# Ethernet_Interface.net
KiCad netlist of a schematic drawn in Altium Designer
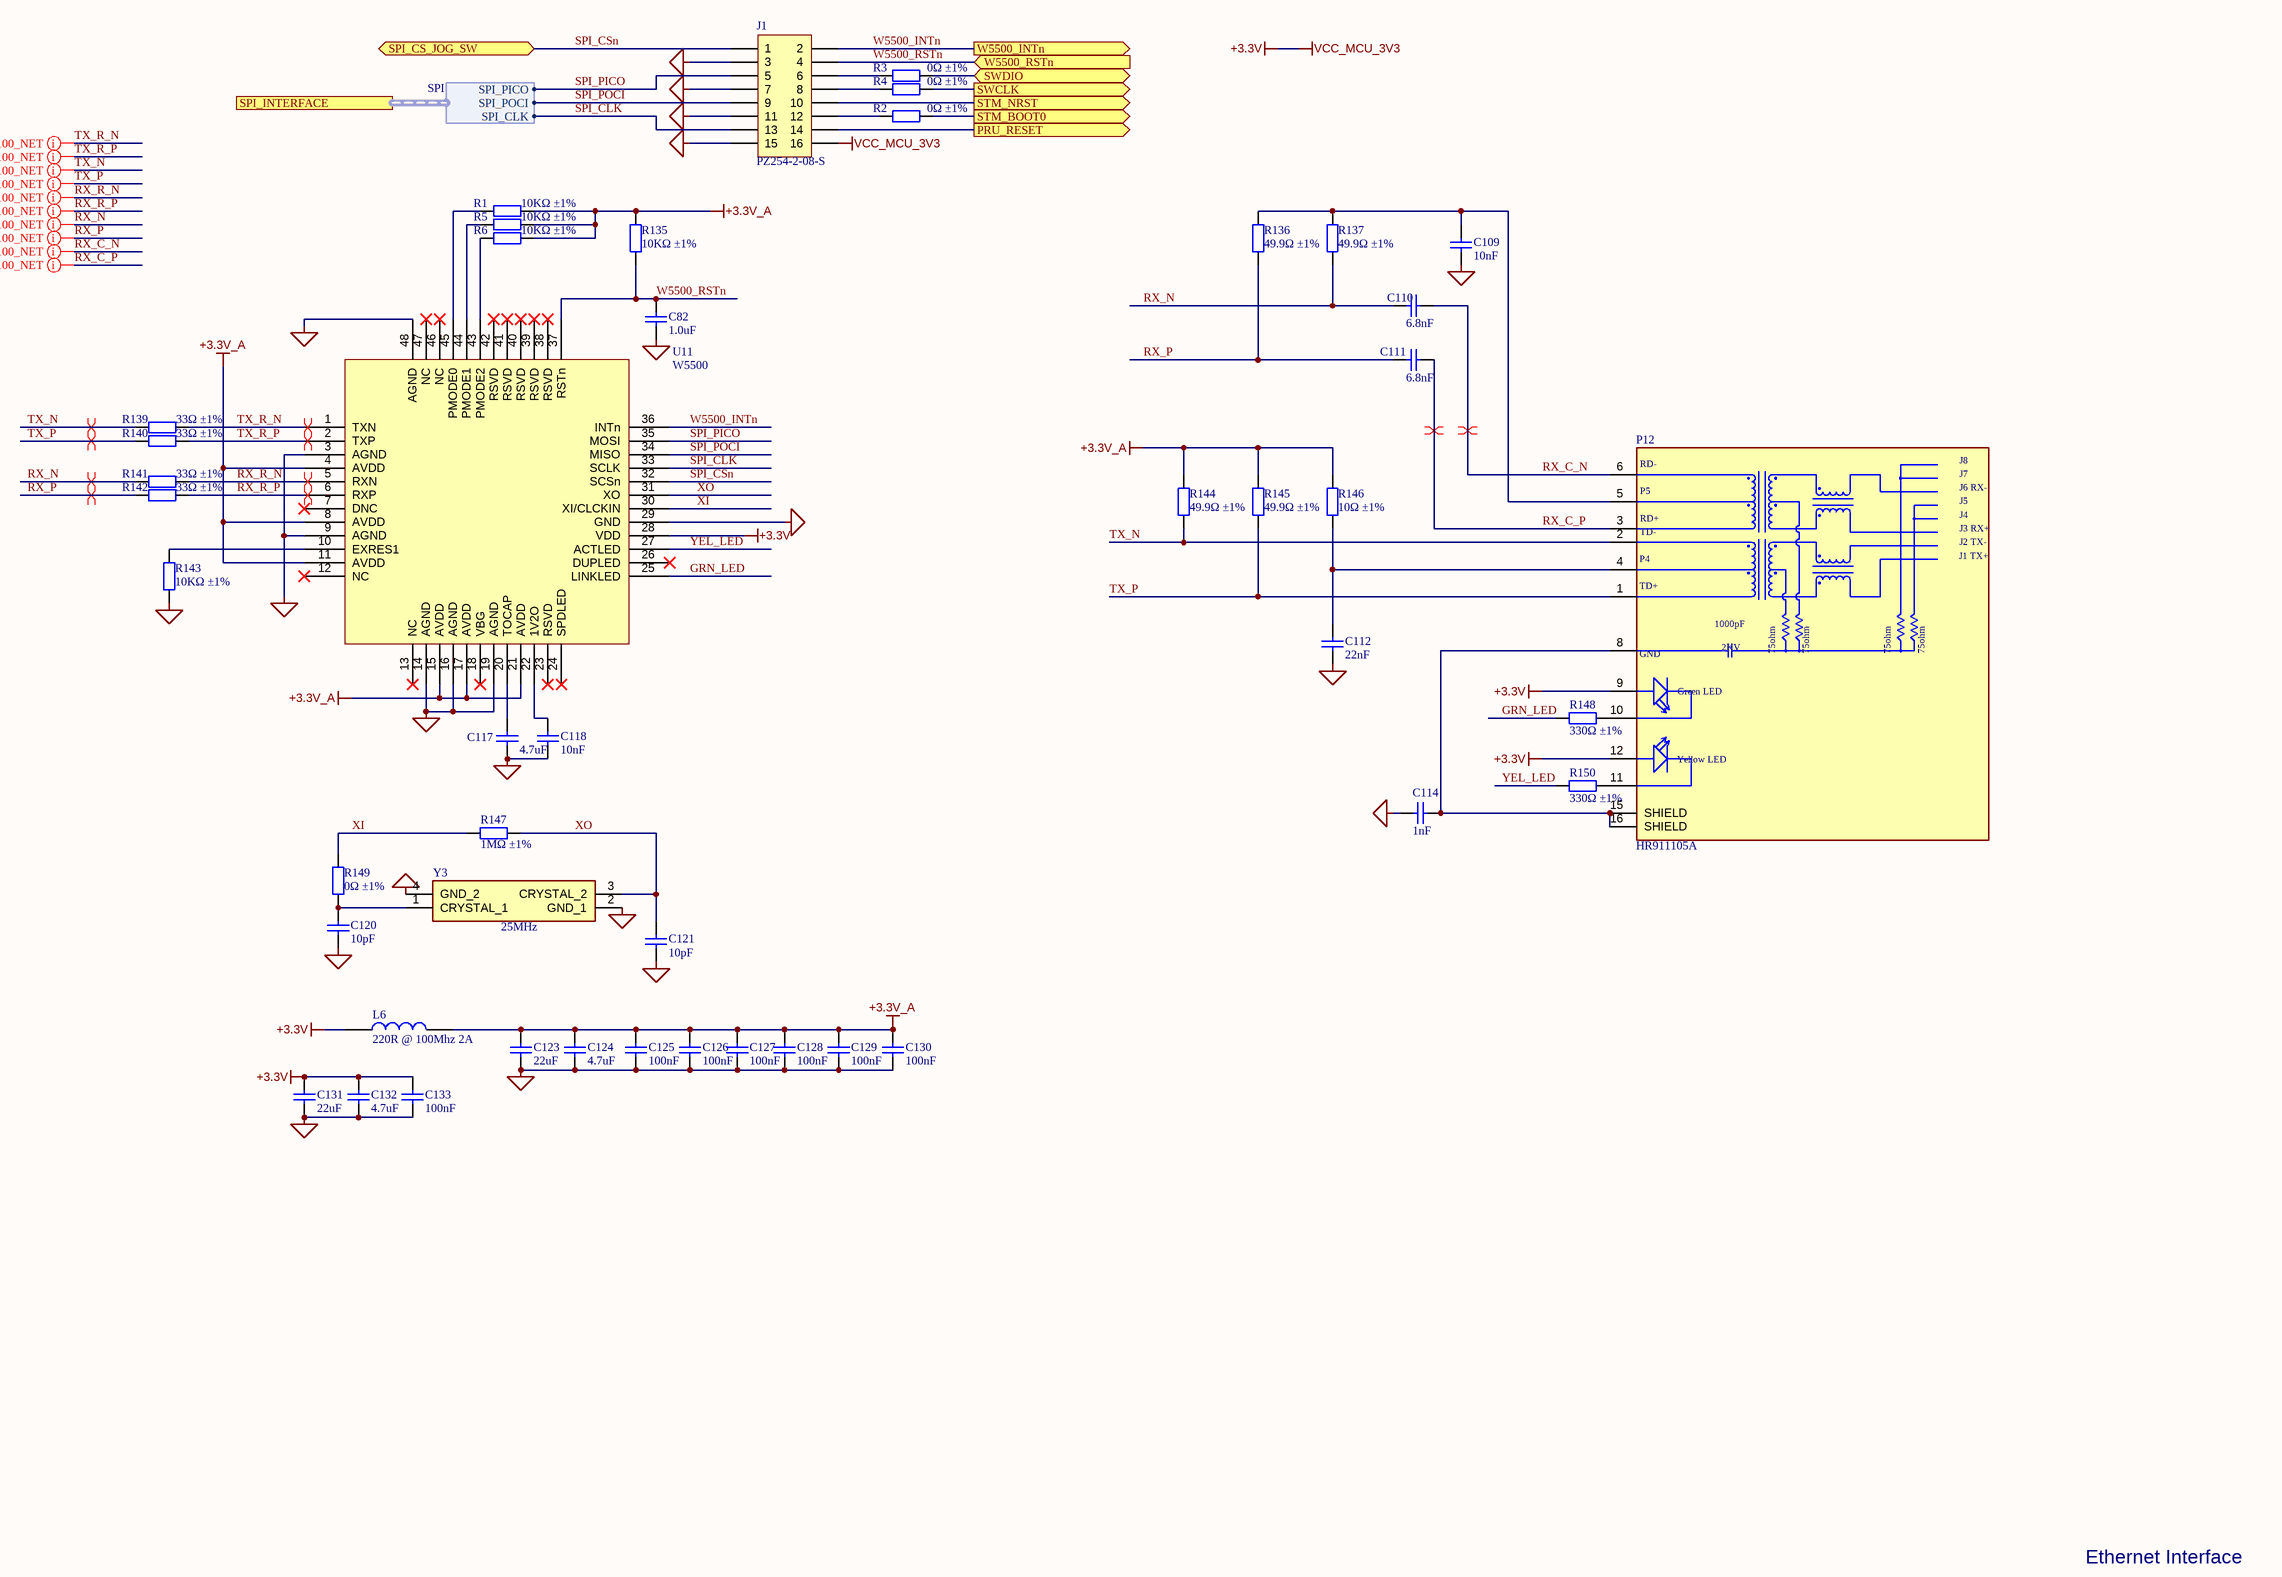
[diagram p0: Ethernet_Interface.SchDoc]

(export (version "E")
  (design (tool "Eeschema 10.0.6"))
  (components
    (comp (ref "C82")
      (value "1.0uF")
      (footprint "0402_C")
      (description "Chip capacitor")
      (fields (field (name "MANUFACTURER") "Samsung Electro-Mechanics") (field (name "TOLERANCE") "10%"))
      (libsource (lib "Cap") (part "0402 1.0uF (105) 10% 25V"))
    )
    (comp (ref "C109")
      (value "10nF")
      (footprint "0402_C")
      (description "Chip capacitors")
      (fields
        (field (name "MANUFACTURER") "Samsung Electro-Mechanics")
        (field (name "MANUFACTURER PART NUMBER") "CL05B103KB5NNNC")
      )
      (libsource (lib "Cap") (part "0402 10nF (103) 10% 50V"))
    )
    (comp (ref "C110")
      (value "6.8nF")
      (footprint "0402_C")
      (description "Chip capacitors")
      (fields
        (field (name "MANUFACTURER") "Guangdong Fenghua Advanced Tech")
        (field (name "MANUFACTURER PART NUMBER") "0402B682K500NT")
      )
      (libsource (lib "Cap") (part "0402 6.8nF (682) 10% 50V"))
    )
    (comp (ref "C111")
      (value "6.8nF")
      (footprint "0402_C")
      (description "Chip capacitors")
      (fields
        (field (name "MANUFACTURER") "Guangdong Fenghua Advanced Tech")
        (field (name "MANUFACTURER PART NUMBER") "0402B682K500NT")
      )
      (libsource (lib "Cap") (part "0402 6.8nF (682) 10% 50V"))
    )
    (comp (ref "C112")
      (value "22nF")
      (footprint "0402_C")
      (description "Chip capacitors")
      (fields
        (field (name "MANUFACTURER") "Guangdong Fenghua Advanced Tech")
        (field (name "MANUFACTURER PART NUMBER") "0402B223K500NT")
      )
      (libsource (lib "Cap") (part "0402 22nF (223) 10% 50V"))
    )
    (comp (ref "C114")
      (value "1nF")
      (footprint "1206_C")
      (description "Chip capacitors")
      (fields
        (field (name "MANUFACTURER") "Samsung Electro-Mechanics")
        (field (name "MANUFACTURER PART NUMBER") "CL31B102KGFNNNE")
      )
      (libsource (lib "Cap") (part "1206 1nF (102) 10% 500V"))
    )
    (comp (ref "C117")
      (value "4.7uF")
      (footprint "0402_C")
      (description "Chip capacitor")
      (fields
        (field (name "MANUFACTURER") "Samsung Electro-Mechanics")
        (field (name "MANUFACTURER PART NUMBER") "CL05A475MP5NRNC")
      )
      (libsource (lib "Cap") (part "0402 4.7uF (475) 20% 10V"))
    )
    (comp (ref "C118")
      (value "10nF")
      (footprint "0402_C")
      (description "Chip capacitors")
      (fields
        (field (name "MANUFACTURER") "Samsung Electro-Mechanics")
        (field (name "MANUFACTURER PART NUMBER") "CL05B103KB5NNNC")
      )
      (libsource (lib "Cap") (part "0402 10nF (103) 10% 50V"))
    )
    (comp (ref "C120")
      (value "10pF")
      (footprint "0402_C")
      (description "Chip capacitors")
      (fields
        (field (name "MANUFACTURER") "Murata Electronics")
        (field (name "MANUFACTURER PART NUMBER") "GRM1555C1H100JA01D")
      )
      (libsource (lib "Sienci_Labs") (part "0402 10pF (100) 5% 50V"))
    )
    (comp (ref "C121")
      (value "10pF")
      (footprint "0402_C")
      (description "Chip capacitors")
      (fields
        (field (name "MANUFACTURER") "Murata Electronics")
        (field (name "MANUFACTURER PART NUMBER") "GRM1555C1H100JA01D")
      )
      (libsource (lib "Sienci_Labs") (part "0402 10pF (100) 5% 50V"))
    )
    (comp (ref "C123")
      (value "22uF")
      (footprint "0805_C")
      (description "25V 22uF X5R ±20% 0805 Multilayer Ceramic Capacitors MLCC - SMD/SMT ROHS")
      (fields (field (name "MANUFACTURER") "Samsung Electro-Mechanics") (field (name "TOLERANCE") "20%"))
      (libsource (lib "Sienci_Labs") (part "0805 22uF (226) 20% 25V"))
    )
    (comp (ref "C124")
      (value "4.7uF")
      (footprint "0603_C")
      (description "16V 4.7uF X5R ±10% 0603 Multilayer Ceramic Capacitors MLCC - SMD/SMT ROHS")
      (fields (field (name "MANUFACTURER") "Samsung Electro-Mechanics") (field (name "TOLERANCE") "10%"))
      (libsource (lib "Sienci_Labs") (part "0603 4.7uF (475) 10% 16V"))
    )
    (comp (ref "C125")
      (value "100nF")
      (footprint "0402_C")
      (description "16V 100nF X7R ±10% 0402 Multilayer Ceramic Capacitors MLCC - SMD/SMT ROHS")
      (fields (field (name "MANUFACTURER") "Samsung Electro-Mechanics") (field (name "TOLERANCE") "10%"))
      (libsource (lib "Sienci_Labs") (part "0402 100nF (104) 10% 16V"))
    )
    (comp (ref "C126")
      (value "100nF")
      (footprint "0402_C")
      (description "16V 100nF X7R ±10% 0402 Multilayer Ceramic Capacitors MLCC - SMD/SMT ROHS")
      (fields (field (name "MANUFACTURER") "Samsung Electro-Mechanics") (field (name "TOLERANCE") "10%"))
      (libsource (lib "Sienci_Labs") (part "0402 100nF (104) 10% 16V"))
    )
    (comp (ref "C127")
      (value "100nF")
      (footprint "0402_C")
      (description "16V 100nF X7R ±10% 0402 Multilayer Ceramic Capacitors MLCC - SMD/SMT ROHS")
      (fields (field (name "MANUFACTURER") "Samsung Electro-Mechanics") (field (name "TOLERANCE") "10%"))
      (libsource (lib "Sienci_Labs") (part "0402 100nF (104) 10% 16V"))
    )
    (comp (ref "C128")
      (value "100nF")
      (footprint "0402_C")
      (description "16V 100nF X7R ±10% 0402 Multilayer Ceramic Capacitors MLCC - SMD/SMT ROHS")
      (fields (field (name "MANUFACTURER") "Samsung Electro-Mechanics") (field (name "TOLERANCE") "10%"))
      (libsource (lib "Sienci_Labs") (part "0402 100nF (104) 10% 16V"))
    )
    (comp (ref "C129")
      (value "100nF")
      (footprint "0402_C")
      (description "16V 100nF X7R ±10% 0402 Multilayer Ceramic Capacitors MLCC - SMD/SMT ROHS")
      (fields (field (name "MANUFACTURER") "Samsung Electro-Mechanics") (field (name "TOLERANCE") "10%"))
      (libsource (lib "Sienci_Labs") (part "0402 100nF (104) 10% 16V"))
    )
    (comp (ref "C130")
      (value "100nF")
      (footprint "0402_C")
      (description "16V 100nF X7R ±10% 0402 Multilayer Ceramic Capacitors MLCC - SMD/SMT ROHS")
      (fields (field (name "MANUFACTURER") "Samsung Electro-Mechanics") (field (name "TOLERANCE") "10%"))
      (libsource (lib "Sienci_Labs") (part "0402 100nF (104) 10% 16V"))
    )
    (comp (ref "C131")
      (value "22uF")
      (footprint "0805_C")
      (description "25V 22uF X5R ±20% 0805 Multilayer Ceramic Capacitors MLCC - SMD/SMT ROHS")
      (fields (field (name "MANUFACTURER") "Samsung Electro-Mechanics") (field (name "TOLERANCE") "20%"))
      (libsource (lib "Sienci_Labs") (part "0805 22uF (226) 20% 25V"))
    )
    (comp (ref "C132")
      (value "4.7uF")
      (footprint "0603_C")
      (description "16V 4.7uF X5R ±10% 0603 Multilayer Ceramic Capacitors MLCC - SMD/SMT ROHS")
      (fields (field (name "MANUFACTURER") "Samsung Electro-Mechanics") (field (name "TOLERANCE") "10%"))
      (libsource (lib "Sienci_Labs") (part "0603 4.7uF (475) 10% 16V"))
    )
    (comp (ref "C133")
      (value "100nF")
      (footprint "0402_C")
      (description "16V 100nF X7R ±10% 0402 Multilayer Ceramic Capacitors MLCC - SMD/SMT ROHS")
      (fields (field (name "MANUFACTURER") "Samsung Electro-Mechanics") (field (name "TOLERANCE") "10%"))
      (libsource (lib "Sienci_Labs") (part "0402 100nF (104) 10% 16V"))
    )
    (comp (ref "J1")
      (value "PZ254-2-08-S")
      (footprint "95278101A16LF")
      (fields (field (name "MANUFACTURER") "HCTL"))
      (libsource (lib "Sienci_Labs") (part "PZ254-2-08-S"))
    )
    (comp (ref "L6")
      (value "220R @ 100Mhz 2A")
      (footprint "0805_R")
      (description "150mΩ ±25% 220Ω@100MHz 0805 Ferrite Beads ROHS")
      (fields
        (field (name "MANUFACTURER PART NUMBER") "CBW201209U221T")
        (field (name "MANUFACTURER") "FH (Guangdong Fenghua Advanced Tech)")
      )
      (libsource (lib "Sienci_Labs") (part "CBW201209U221T"))
    )
    (comp (ref "P12")
      (value "HR911105A")
      (footprint "HANRUN_HR911105A")
      (description "HR911105A Ethernet Interface Arduino Platform Evaluation Expansion Board")
      (fields (field (name "MANUFACTURER") "DFRobot"))
      (libsource (lib "Sienci_Labs") (part "HR911105A"))
    )
    (comp (ref "R1")
      (value "10KΩ ±1%")
      (footprint "0402_R")
      (description "Chip resistor")
      (fields
        (field (name "MANUFACTURER") "Uniroyal Elec")
        (field (name "MANUFACTURER PART NUMBER") "0402WGF1002TCE")
      )
      (libsource (lib "Sienci_Labs") (part "0402 10K (1002) 1%"))
    )
    (comp (ref "R2")
      (value "0Ω ±1%")
      (footprint "0603_R")
      (description "Chip resistor")
      (fields
        (field (name "MANUFACTURER") "Uniroyal Elec")
        (field (name "MANUFACTURER PART NUMBER") "0603WAF0000T5E")
      )
      (libsource (lib "Sienci_Labs") (part "0603 0R (0R0) 1%"))
    )
    (comp (ref "R3")
      (value "0Ω ±1%")
      (footprint "0603_R")
      (description "Chip resistor")
      (fields
        (field (name "MANUFACTURER") "Uniroyal Elec")
        (field (name "MANUFACTURER PART NUMBER") "0603WAF0000T5E")
      )
      (libsource (lib "Sienci_Labs") (part "0603 0R (0R0) 1%"))
    )
    (comp (ref "R4")
      (value "0Ω ±1%")
      (footprint "0603_R")
      (description "Chip resistor")
      (fields
        (field (name "MANUFACTURER") "Uniroyal Elec")
        (field (name "MANUFACTURER PART NUMBER") "0603WAF0000T5E")
      )
      (libsource (lib "Sienci_Labs") (part "0603 0R (0R0) 1%"))
    )
    (comp (ref "R5")
      (value "10KΩ ±1%")
      (footprint "0402_R")
      (description "Chip resistor")
      (fields
        (field (name "MANUFACTURER") "Uniroyal Elec")
        (field (name "MANUFACTURER PART NUMBER") "0402WGF1002TCE")
      )
      (libsource (lib "Sienci_Labs") (part "0402 10K (1002) 1%"))
    )
    (comp (ref "R6")
      (value "10KΩ ±1%")
      (footprint "0402_R")
      (description "Chip resistor")
      (fields
        (field (name "MANUFACTURER") "Uniroyal Elec")
        (field (name "MANUFACTURER PART NUMBER") "0402WGF1002TCE")
      )
      (libsource (lib "Sienci_Labs") (part "0402 10K (1002) 1%"))
    )
    (comp (ref "R135")
      (value "10KΩ ±1%")
      (footprint "0402_R")
      (description "Chip resistor")
      (fields
        (field (name "MANUFACTURER") "Uniroyal Elec")
        (field (name "MANUFACTURER PART NUMBER") "0402WGF1002TCE")
      )
      (libsource (lib "") (part "0402 10K (1002) 1%_1"))
    )
    (comp (ref "R136")
      (value "49.9Ω ±1%")
      (footprint "0402_R")
      (description "Chip resistor")
      (fields
        (field (name "MANUFACTURER") "Uniroyal Elec")
        (field (name "MANUFACTURER PART NUMBER") "0402WGF499JTCE")
      )
      (libsource (lib "RES") (part "0402 49.9R (49R9) 1%"))
    )
    (comp (ref "R137")
      (value "49.9Ω ±1%")
      (footprint "0402_R")
      (description "Chip resistor")
      (fields
        (field (name "MANUFACTURER") "Uniroyal Elec")
        (field (name "MANUFACTURER PART NUMBER") "0402WGF499JTCE")
      )
      (libsource (lib "RES") (part "0402 49.9R (49R9) 1%"))
    )
    (comp (ref "R139")
      (value "33Ω ±1%")
      (footprint "0402_R")
      (description "Chip resistor")
      (fields
        (field (name "MANUFACTURER") "Uniroyal Elec")
        (field (name "MANUFACTURER PART NUMBER") "0402WGF330JTCE")
      )
      (libsource (lib "RES") (part "0402 33R (33R0) 1%"))
    )
    (comp (ref "R140")
      (value "33Ω ±1%")
      (footprint "0402_R")
      (description "Chip resistor")
      (fields
        (field (name "MANUFACTURER") "Uniroyal Elec")
        (field (name "MANUFACTURER PART NUMBER") "0402WGF330JTCE")
      )
      (libsource (lib "RES") (part "0402 33R (33R0) 1%"))
    )
    (comp (ref "R141")
      (value "33Ω ±1%")
      (footprint "0402_R")
      (description "Chip resistor")
      (fields
        (field (name "MANUFACTURER") "Uniroyal Elec")
        (field (name "MANUFACTURER PART NUMBER") "0402WGF330JTCE")
      )
      (libsource (lib "RES") (part "0402 33R (33R0) 1%"))
    )
    (comp (ref "R142")
      (value "33Ω ±1%")
      (footprint "0402_R")
      (description "Chip resistor")
      (fields
        (field (name "MANUFACTURER") "Uniroyal Elec")
        (field (name "MANUFACTURER PART NUMBER") "0402WGF330JTCE")
      )
      (libsource (lib "RES") (part "0402 33R (33R0) 1%"))
    )
    (comp (ref "R143")
      (value "10KΩ ±1%")
      (footprint "0603_R")
      (description "Chip resistor")
      (fields
        (field (name "MANUFACTURER") "Uniroyal Elec")
        (field (name "MANUFACTURER PART NUMBER") "0603WAF1002T5E")
      )
      (libsource (lib "Sienci_Labs") (part "0603 10K (1002) 1%"))
    )
    (comp (ref "R144")
      (value "49.9Ω ±1%")
      (footprint "0402_R")
      (description "Chip resistor")
      (fields
        (field (name "MANUFACTURER") "Uniroyal Elec")
        (field (name "MANUFACTURER PART NUMBER") "0402WGF499JTCE")
      )
      (libsource (lib "RES") (part "0402 49.9R (49R9) 1%"))
    )
    (comp (ref "R145")
      (value "49.9Ω ±1%")
      (footprint "0402_R")
      (description "Chip resistor")
      (fields
        (field (name "MANUFACTURER") "Uniroyal Elec")
        (field (name "MANUFACTURER PART NUMBER") "0402WGF499JTCE")
      )
      (libsource (lib "RES") (part "0402 49.9R (49R9) 1%"))
    )
    (comp (ref "R146")
      (value "10Ω ±1%")
      (footprint "0402_R")
      (description "Chip resistor")
      (fields
        (field (name "MANUFACTURER") "Uniroyal Elec")
        (field (name "MANUFACTURER PART NUMBER") "0402WGF100JTCE")
      )
      (libsource (lib "RES") (part "0402 10R (10R0) 1%"))
    )
    (comp (ref "R147")
      (value "1MΩ ±1%")
      (footprint "0402_R")
      (description "Chip resistor")
      (fields
        (field (name "MANUFACTURER") "Uniroyal Elec")
        (field (name "MANUFACTURER PART NUMBER") "0402WGF1004TCE")
      )
      (libsource (lib "RES") (part "0402 1M (1004) 1%"))
    )
    (comp (ref "R148")
      (value "330Ω ±1%")
      (footprint "0402_R")
      (description "Chip resistor")
      (fields
        (field (name "MANUFACTURER") "Uniroyal Elec")
        (field (name "MANUFACTURER PART NUMBER") "0402WGF3300TCE")
      )
      (libsource (lib "RES") (part "0402 330R (3300) 1%"))
    )
    (comp (ref "R149")
      (value "0Ω ±1%")
      (footprint "0402_R")
      (description "Chip resistor")
      (fields
        (field (name "MANUFACTURER") "Uniroyal Elec")
        (field (name "MANUFACTURER PART NUMBER") "0402WGF0000TCE")
      )
      (libsource (lib "RES") (part "0402 0R (0R0) 1%"))
    )
    (comp (ref "R150")
      (value "330Ω ±1%")
      (footprint "0402_R")
      (description "Chip resistor")
      (fields
        (field (name "MANUFACTURER") "Uniroyal Elec")
        (field (name "MANUFACTURER PART NUMBER") "0402WGF3300TCE")
      )
      (libsource (lib "RES") (part "0402 330R (3300) 1%"))
    )
    (comp (ref "U11")
      (value "W5500")
      (footprint "LQFP-48_7x7x05P")
      (description "Ethernet Controllers 2.97V ~ 3.63V 10/100 Base-T/TX PHY SPI LQFP-48_7x7x05P Ethernet ICs ROHS")
      (fields (field (name "MANUFACTURER") "WIZNET"))
      (libsource (lib "Sienci_Labs") (part "W5500_[C32843]"))
    )
    (comp (ref "Y3")
      (value "25MHz")
      (footprint "YSX321SL")
      (description "25MHz SMD Crystal Resonator 20pF ±10ppm ±30ppm -40℃~+85℃ SMD3225-4P Crystals ROHS")
      (fields
        (field (name "MANUFACTURER") "Yangxing Tech")
        (field (name "MANUFACTURER PART NUMBER") "X322525MSB4SI")
      )
      (libsource (lib "Sienci_Labs") (part "X322525MSB4SI"))
    )
  )
  (nets
    (net (code "2") (name "+3.3V") (class "Default")
      (node (ref "C131") (pin "2") (pinfunction "2_2") (pintype "passive"))
      (node (ref "C132") (pin "2") (pinfunction "2_2") (pintype "passive"))
      (node (ref "C133") (pin "2") (pinfunction "2_2") (pintype "passive"))
      (node (ref "J1") (pin "16") (pinfunction "16_16") (pintype "passive"))
      (node (ref "L6") (pin "1") (pinfunction "1_1") (pintype "passive"))
      (node (ref "P12") (pin "12") (pinfunction "YA_12") (pintype "passive"))
      (node (ref "P12") (pin "9") (pinfunction "GA_9") (pintype "passive"))
      (node (ref "U11") (pin "28") (pinfunction "VDD_28") (pintype "passive"))
    )
    (net (code "3") (name "+3.3V_A") (class "Default")
      (node (ref "C123") (pin "2") (pinfunction "2_2") (pintype "passive"))
      (node (ref "C124") (pin "2") (pinfunction "2_2") (pintype "passive"))
      (node (ref "C125") (pin "2") (pinfunction "2_2") (pintype "passive"))
      (node (ref "C126") (pin "2") (pinfunction "2_2") (pintype "passive"))
      (node (ref "C127") (pin "2") (pinfunction "2_2") (pintype "passive"))
      (node (ref "C128") (pin "2") (pinfunction "2_2") (pintype "passive"))
      (node (ref "C129") (pin "2") (pinfunction "2_2") (pintype "passive"))
      (node (ref "C130") (pin "2") (pinfunction "2_2") (pintype "passive"))
      (node (ref "L6") (pin "2") (pinfunction "2_2") (pintype "passive"))
      (node (ref "R1") (pin "1") (pinfunction "1_1") (pintype "passive"))
      (node (ref "R135") (pin "1") (pinfunction "1_1") (pintype "passive"))
      (node (ref "R144") (pin "1") (pinfunction "1_1") (pintype "passive"))
      (node (ref "R145") (pin "1") (pinfunction "1_1") (pintype "passive"))
      (node (ref "R146") (pin "1") (pinfunction "1_1") (pintype "passive"))
      (node (ref "R5") (pin "1") (pinfunction "1_1") (pintype "passive"))
      (node (ref "R6") (pin "1") (pinfunction "1_1") (pintype "passive"))
      (node (ref "U11") (pin "11") (pinfunction "AVDD_11") (pintype "passive"))
      (node (ref "U11") (pin "15") (pinfunction "AVDD_15") (pintype "passive"))
      (node (ref "U11") (pin "17") (pinfunction "AVDD_17") (pintype "passive"))
      (node (ref "U11") (pin "21") (pinfunction "AVDD_21") (pintype "passive"))
      (node (ref "U11") (pin "4") (pinfunction "AVDD_4") (pintype "passive"))
      (node (ref "U11") (pin "8") (pinfunction "AVDD_8") (pintype "passive"))
    )
    (net (code "4") (name "/GRN_LED") (class "Default")
      (node (ref "R148") (pin "1") (pinfunction "1_1") (pintype "passive"))
      (node (ref "U11") (pin "25") (pinfunction "LINKLED_25") (pintype "passive"))
    )
    (net (code "5") (name "/PRU_RESET") (class "Default")
      (node (ref "J1") (pin "14") (pinfunction "14_14") (pintype "passive"))
    )
    (net (code "6") (name "/RX_C_N") (class "Default")
      (node (ref "C110") (pin "1") (pinfunction "1_1") (pintype "passive"))
      (node (ref "P12") (pin "6") (pinfunction "RD-_6") (pintype "passive"))
    )
    (net (code "7") (name "/RX_C_P") (class "Default")
      (node (ref "C111") (pin "1") (pinfunction "1_1") (pintype "passive"))
      (node (ref "P12") (pin "3") (pinfunction "RD+_3") (pintype "passive"))
    )
    (net (code "8") (name "/RX_N") (class "Default")
      (node (ref "C110") (pin "2") (pinfunction "2_2") (pintype "passive"))
      (node (ref "R137") (pin "2") (pinfunction "2_2") (pintype "passive"))
      (node (ref "R141") (pin "1") (pinfunction "1_1") (pintype "passive"))
    )
    (net (code "9") (name "/RX_P") (class "Default")
      (node (ref "C111") (pin "2") (pinfunction "2_2") (pintype "passive"))
      (node (ref "R136") (pin "2") (pinfunction "2_2") (pintype "passive"))
      (node (ref "R142") (pin "1") (pinfunction "1_1") (pintype "passive"))
    )
    (net (code "10") (name "/RX_R_N") (class "Default")
      (node (ref "R141") (pin "2") (pinfunction "2_2") (pintype "passive"))
      (node (ref "U11") (pin "5") (pinfunction "RXN_5") (pintype "passive"))
    )
    (net (code "11") (name "/RX_R_P") (class "Default")
      (node (ref "R142") (pin "2") (pinfunction "2_2") (pintype "passive"))
      (node (ref "U11") (pin "6") (pinfunction "RXP_6") (pintype "passive"))
    )
    (net (code "12") (name "/SPI_CLK") (class "Default")
      (node (ref "J1") (pin "13") (pinfunction "13_13") (pintype "passive"))
      (node (ref "U11") (pin "33") (pinfunction "SCLK_33") (pintype "passive"))
    )
    (net (code "13") (name "/SPI_CSn") (class "Default")
      (node (ref "J1") (pin "1") (pinfunction "1_1") (pintype "passive"))
      (node (ref "U11") (pin "32") (pinfunction "SCSn_32") (pintype "passive"))
    )
    (net (code "14") (name "/SPI_PICO") (class "Default")
      (node (ref "J1") (pin "5") (pinfunction "5_5") (pintype "passive"))
      (node (ref "U11") (pin "35") (pinfunction "MOSI_35") (pintype "passive"))
    )
    (net (code "15") (name "/SPI_POCI") (class "Default")
      (node (ref "J1") (pin "9") (pinfunction "9_9") (pintype "passive"))
      (node (ref "U11") (pin "34") (pinfunction "MISO_34") (pintype "passive"))
    )
    (net (code "16") (name "/STM_BOOT0") (class "Default")
      (node (ref "R2") (pin "1") (pinfunction "1_1") (pintype "passive"))
    )
    (net (code "17") (name "/STM_NRST") (class "Default")
      (node (ref "J1") (pin "10") (pinfunction "10_10") (pintype "passive"))
    )
    (net (code "18") (name "/SWCLK") (class "Default")
      (node (ref "R4") (pin "1") (pinfunction "1_1") (pintype "passive"))
    )
    (net (code "19") (name "/SWDIO") (class "Default")
      (node (ref "R3") (pin "1") (pinfunction "1_1") (pintype "passive"))
    )
    (net (code "20") (name "/TX_N") (class "Default")
      (node (ref "P12") (pin "2") (pinfunction "TD-_2") (pintype "passive"))
      (node (ref "R139") (pin "1") (pinfunction "1_1") (pintype "passive"))
      (node (ref "R144") (pin "2") (pinfunction "2_2") (pintype "passive"))
    )
    (net (code "21") (name "/TX_P") (class "Default")
      (node (ref "P12") (pin "1") (pinfunction "TD+_1") (pintype "passive"))
      (node (ref "R140") (pin "1") (pinfunction "1_1") (pintype "passive"))
      (node (ref "R145") (pin "2") (pinfunction "2_2") (pintype "passive"))
    )
    (net (code "22") (name "/TX_R_N") (class "Default")
      (node (ref "R139") (pin "2") (pinfunction "2_2") (pintype "passive"))
      (node (ref "U11") (pin "1") (pinfunction "TXN_1") (pintype "passive"))
    )
    (net (code "23") (name "/TX_R_P") (class "Default")
      (node (ref "R140") (pin "2") (pinfunction "2_2") (pintype "passive"))
      (node (ref "U11") (pin "2") (pinfunction "TXP_2") (pintype "passive"))
    )
    (net (code "24") (name "/W5500_INTn") (class "Default")
      (node (ref "J1") (pin "2") (pinfunction "2_2") (pintype "passive"))
      (node (ref "U11") (pin "36") (pinfunction "INTn_36") (pintype "passive"))
    )
    (net (code "25") (name "/W5500_RSTn") (class "Default")
      (node (ref "C82") (pin "2") (pinfunction "2_2") (pintype "passive"))
      (node (ref "J1") (pin "4") (pinfunction "4_4") (pintype "passive"))
      (node (ref "R135") (pin "2") (pinfunction "2_2") (pintype "passive"))
      (node (ref "U11") (pin "37") (pinfunction "RSTn_37") (pintype "passive"))
    )
    (net (code "26") (name "/XI") (class "Default")
      (node (ref "R147") (pin "1") (pinfunction "1_1") (pintype "passive"))
      (node (ref "R149") (pin "1") (pinfunction "1_1") (pintype "passive"))
      (node (ref "U11") (pin "30") (pinfunction "XI/CLCKIN_30") (pintype "passive"))
    )
    (net (code "27") (name "/XO") (class "Default")
      (node (ref "C121") (pin "2") (pinfunction "2_2") (pintype "passive"))
      (node (ref "R147") (pin "2") (pinfunction "2_2") (pintype "passive"))
      (node (ref "U11") (pin "31") (pinfunction "XO_31") (pintype "passive"))
      (node (ref "Y3") (pin "3") (pinfunction "CRYSTAL_2_3") (pintype "passive"))
    )
    (net (code "28") (name "/YEL_LED") (class "Default")
      (node (ref "R150") (pin "1") (pinfunction "1_1") (pintype "passive"))
      (node (ref "U11") (pin "27") (pinfunction "ACTLED_27") (pintype "passive"))
    )
    (net (code "30") (name "MCU_GND") (class "Default")
      (node (ref "C109") (pin "1") (pinfunction "1_1") (pintype "passive"))
      (node (ref "C112") (pin "1") (pinfunction "1_1") (pintype "passive"))
      (node (ref "C114") (pin "1") (pinfunction "1_1") (pintype "passive"))
      (node (ref "C117") (pin "1") (pinfunction "1_1") (pintype "passive"))
      (node (ref "C118") (pin "1") (pinfunction "1_1") (pintype "passive"))
      (node (ref "C120") (pin "1") (pinfunction "1_1") (pintype "passive"))
      (node (ref "C121") (pin "1") (pinfunction "1_1") (pintype "passive"))
      (node (ref "C123") (pin "1") (pinfunction "1_1") (pintype "passive"))
      (node (ref "C124") (pin "1") (pinfunction "1_1") (pintype "passive"))
      (node (ref "C125") (pin "1") (pinfunction "1_1") (pintype "passive"))
      (node (ref "C126") (pin "1") (pinfunction "1_1") (pintype "passive"))
      (node (ref "C127") (pin "1") (pinfunction "1_1") (pintype "passive"))
      (node (ref "C128") (pin "1") (pinfunction "1_1") (pintype "passive"))
      (node (ref "C129") (pin "1") (pinfunction "1_1") (pintype "passive"))
      (node (ref "C130") (pin "1") (pinfunction "1_1") (pintype "passive"))
      (node (ref "C131") (pin "1") (pinfunction "1_1") (pintype "passive"))
      (node (ref "C132") (pin "1") (pinfunction "1_1") (pintype "passive"))
      (node (ref "C133") (pin "1") (pinfunction "1_1") (pintype "passive"))
      (node (ref "C82") (pin "1") (pinfunction "1_1") (pintype "passive"))
      (node (ref "J1") (pin "11") (pinfunction "11_11") (pintype "passive"))
      (node (ref "J1") (pin "15") (pinfunction "15_15") (pintype "passive"))
      (node (ref "J1") (pin "3") (pinfunction "3_3") (pintype "passive"))
      (node (ref "J1") (pin "7") (pinfunction "7_7") (pintype "passive"))
      (node (ref "R143") (pin "1") (pinfunction "1_1") (pintype "passive"))
      (node (ref "U11") (pin "14") (pinfunction "AGND_14") (pintype "passive"))
      (node (ref "U11") (pin "16") (pinfunction "AGND_16") (pintype "passive"))
      (node (ref "U11") (pin "19") (pinfunction "AGND_19") (pintype "passive"))
      (node (ref "U11") (pin "29") (pinfunction "GND_29") (pintype "passive"))
      (node (ref "U11") (pin "3") (pinfunction "AGND_3") (pintype "passive"))
      (node (ref "U11") (pin "48") (pinfunction "AGND_48") (pintype "passive"))
      (node (ref "U11") (pin "9") (pinfunction "AGND_9") (pintype "passive"))
      (node (ref "Y3") (pin "2") (pinfunction "GND_1_2") (pintype "passive"))
      (node (ref "Y3") (pin "4") (pinfunction "GND_2_4") (pintype "passive"))
    )
    (net (code "31") (name "Net-(J1-Pad6)") (class "Default")
      (node (ref "J1") (pin "6") (pinfunction "6_6") (pintype "passive"))
      (node (ref "R3") (pin "2") (pinfunction "2_2") (pintype "passive"))
    )
    (net (code "32") (name "Net-(J1-Pad8)") (class "Default")
      (node (ref "J1") (pin "8") (pinfunction "8_8") (pintype "passive"))
      (node (ref "R4") (pin "2") (pinfunction "2_2") (pintype "passive"))
    )
    (net (code "33") (name "Net-(J1-Pad12)") (class "Default")
      (node (ref "J1") (pin "12") (pinfunction "12_12") (pintype "passive"))
      (node (ref "R2") (pin "2") (pinfunction "2_2") (pintype "passive"))
    )
    (net (code "34") (name "Net-(P12-GC)") (class "Default")
      (node (ref "P12") (pin "10") (pinfunction "GC_10") (pintype "passive"))
      (node (ref "R148") (pin "2") (pinfunction "2_2") (pintype "passive"))
    )
    (net (code "35") (name "Net-(P12-GND)") (class "Default")
      (node (ref "C114") (pin "2") (pinfunction "2_2") (pintype "passive"))
      (node (ref "P12") (pin "15") (pinfunction "SHIELD_15") (pintype "passive"))
      (node (ref "P12") (pin "16") (pinfunction "SHIELD_16") (pintype "passive"))
      (node (ref "P12") (pin "8") (pinfunction "GND_8") (pintype "power_in"))
    )
    (net (code "36") (name "Net-(P12-P4)") (class "Default")
      (node (ref "C112") (pin "2") (pinfunction "2_2") (pintype "passive"))
      (node (ref "P12") (pin "4") (pinfunction "P4_4") (pintype "passive"))
      (node (ref "R146") (pin "2") (pinfunction "2_2") (pintype "passive"))
    )
    (net (code "37") (name "Net-(P12-P5)") (class "Default")
      (node (ref "C109") (pin "2") (pinfunction "2_2") (pintype "passive"))
      (node (ref "P12") (pin "5") (pinfunction "P5_5") (pintype "passive"))
      (node (ref "R136") (pin "1") (pinfunction "1_1") (pintype "passive"))
      (node (ref "R137") (pin "1") (pinfunction "1_1") (pintype "passive"))
    )
    (net (code "38") (name "Net-(P12-YC)") (class "Default")
      (node (ref "P12") (pin "11") (pinfunction "YC_11") (pintype "passive"))
      (node (ref "R150") (pin "2") (pinfunction "2_2") (pintype "passive"))
    )
    (net (code "39") (name "Net-(U11-1V2O)") (class "Default")
      (node (ref "C118") (pin "2") (pinfunction "2_2") (pintype "passive"))
      (node (ref "U11") (pin "22") (pinfunction "1V2O_22") (pintype "passive"))
    )
    (net (code "40") (name "Net-(U11-EXRES1)") (class "Default")
      (node (ref "R143") (pin "2") (pinfunction "2_2") (pintype "passive"))
      (node (ref "U11") (pin "10") (pinfunction "EXRES1_10") (pintype "passive"))
    )
    (net (code "41") (name "Net-(U11-PMODE0)") (class "Default")
      (node (ref "R1") (pin "2") (pinfunction "2_2") (pintype "passive"))
      (node (ref "U11") (pin "45") (pinfunction "PMODE0_45") (pintype "passive"))
    )
    (net (code "42") (name "Net-(U11-PMODE1)") (class "Default")
      (node (ref "R5") (pin "2") (pinfunction "2_2") (pintype "passive"))
      (node (ref "U11") (pin "44") (pinfunction "PMODE1_44") (pintype "passive"))
    )
    (net (code "43") (name "Net-(U11-PMODE2)") (class "Default")
      (node (ref "R6") (pin "2") (pinfunction "2_2") (pintype "passive"))
      (node (ref "U11") (pin "43") (pinfunction "PMODE2_43") (pintype "passive"))
    )
    (net (code "44") (name "Net-(U11-TOCAP)") (class "Default")
      (node (ref "C117") (pin "2") (pinfunction "2_2") (pintype "passive"))
      (node (ref "U11") (pin "20") (pinfunction "TOCAP_20") (pintype "passive"))
    )
    (net (code "45") (name "Net-(Y3-CRYSTAL_1)") (class "Default")
      (node (ref "C120") (pin "2") (pinfunction "2_2") (pintype "passive"))
      (node (ref "R149") (pin "2") (pinfunction "2_2") (pintype "passive"))
      (node (ref "Y3") (pin "1") (pinfunction "CRYSTAL_1_1") (pintype "passive"))
    )
    (net (code "46") (name "unconnected-(U11-DNC-Pad7)") (class "Default")
      (node (ref "U11") (pin "7") (pinfunction "DNC_7") (pintype "passive+no_connect"))
    )
    (net (code "47") (name "unconnected-(U11-DUPLED-Pad26)") (class "Default")
      (node (ref "U11") (pin "26") (pinfunction "DUPLED_26") (pintype "passive+no_connect"))
    )
    (net (code "48") (name "unconnected-(U11-NC-Pad12)") (class "Default")
      (node (ref "U11") (pin "12") (pinfunction "NC_12") (pintype "passive+no_connect"))
    )
    (net (code "49") (name "unconnected-(U11-NC-Pad13)") (class "Default")
      (node (ref "U11") (pin "13") (pinfunction "NC_13") (pintype "passive+no_connect"))
    )
    (net (code "50") (name "unconnected-(U11-NC-Pad46)") (class "Default")
      (node (ref "U11") (pin "46") (pinfunction "NC_46") (pintype "passive+no_connect"))
    )
    (net (code "51") (name "unconnected-(U11-NC-Pad47)") (class "Default")
      (node (ref "U11") (pin "47") (pinfunction "NC_47") (pintype "passive+no_connect"))
    )
    (net (code "52") (name "unconnected-(U11-RSVD-Pad23)") (class "Default")
      (node (ref "U11") (pin "23") (pinfunction "RSVD_23") (pintype "passive+no_connect"))
    )
    (net (code "53") (name "unconnected-(U11-RSVD-Pad38)") (class "Default")
      (node (ref "U11") (pin "38") (pinfunction "RSVD_38") (pintype "passive+no_connect"))
    )
    (net (code "54") (name "unconnected-(U11-RSVD-Pad39)") (class "Default")
      (node (ref "U11") (pin "39") (pinfunction "RSVD_39") (pintype "passive+no_connect"))
    )
    (net (code "55") (name "unconnected-(U11-RSVD-Pad40)") (class "Default")
      (node (ref "U11") (pin "40") (pinfunction "RSVD_40") (pintype "passive+no_connect"))
    )
    (net (code "56") (name "unconnected-(U11-RSVD-Pad41)") (class "Default")
      (node (ref "U11") (pin "41") (pinfunction "RSVD_41") (pintype "passive+no_connect"))
    )
    (net (code "57") (name "unconnected-(U11-RSVD-Pad42)") (class "Default")
      (node (ref "U11") (pin "42") (pinfunction "RSVD_42") (pintype "passive+no_connect"))
    )
    (net (code "58") (name "unconnected-(U11-SPDLED-Pad24)") (class "Default")
      (node (ref "U11") (pin "24") (pinfunction "SPDLED_24") (pintype "passive+no_connect"))
    )
    (net (code "59") (name "unconnected-(U11-VBG-Pad18)") (class "Default")
      (node (ref "U11") (pin "18") (pinfunction "VBG_18") (pintype "passive+no_connect"))
    )
  )
)
